# SCH004.net
KiCad netlist of a schematic drawn in Altium Designer
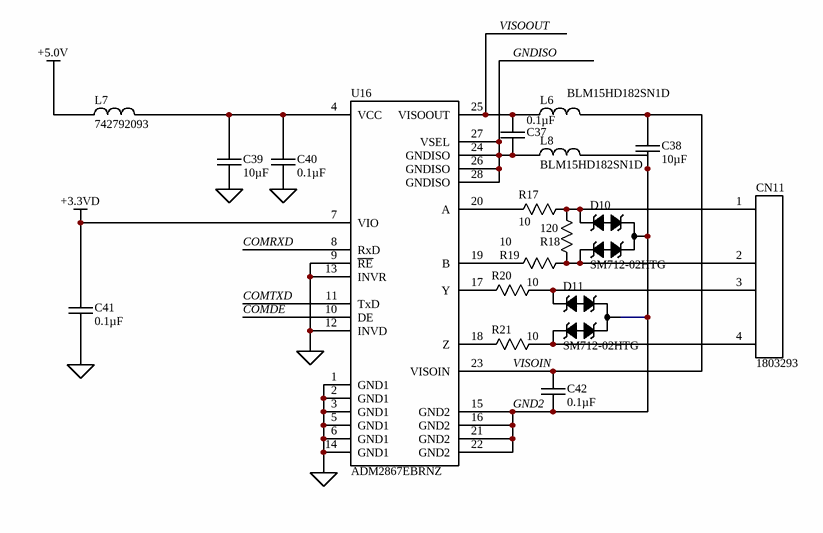
[diagram p0: SCH004.SchDoc]

(export (version "E")
  (design (tool "Eeschema 10.0.6"))
  (components
    (comp (ref "C37")
      (value "0.1µF")
      (footprint "CAPC2012X14N")
      (description "0.1µF/50V/±10% X7R Ceramic Chip Capacitor")
      (fields (field (name "MANUFACTURER") "Taiyo Yuden") (field (name "PARTNUMBER") "UMK212B7104KGHT"))
      (libsource (lib "EM411-202401-RMC001-001") (part "UMK212B7104KGHT"))
    )
    (comp (ref "C38")
      (value "10µF")
      (footprint "CAPC2012X14N")
      (description "10µF/25V 10% X5R Multi-Layer Ceramic Capacitor")
      (fields
        (field (name "MANUFACTURER") "Samsung Electro-Mechanics")
        (field (name "PARTNUMBER") "CL21A106KAFN3NE")
      )
      (libsource (lib "EM411-202401-RMC001-000-20240213-T10") (part "CL21A106KAFN3NE"))
    )
    (comp (ref "C39")
      (value "10µF")
      (footprint "CAPC2012X14N")
      (description "10µF/25V 10% X5R Multi-Layer Ceramic Capacitor")
      (fields
        (field (name "MANUFACTURER") "Samsung Electro-Mechanics")
        (field (name "PARTNUMBER") "CL21A106KAFN3NE")
      )
      (libsource (lib "EM411-202401-RMC001-000-20240213-T10") (part "CL21A106KAFN3NE"))
    )
    (comp (ref "C40")
      (value "0.1µF")
      (footprint "CAPC2012X14N")
      (description "0.1µF/50V/±10% X7R Ceramic Chip Capacitor")
      (fields (field (name "MANUFACTURER") "Taiyo Yuden") (field (name "PARTNUMBER") "UMK212B7104KGHT"))
      (libsource (lib "EM411-202401-RMC001-001") (part "UMK212B7104KGHT"))
    )
    (comp (ref "C41")
      (value "0.1µF")
      (footprint "CAPC2012X14N")
      (description "0.1µF/50V/±10% X7R Ceramic Chip Capacitor")
      (fields (field (name "MANUFACTURER") "Taiyo Yuden") (field (name "PARTNUMBER") "UMK212B7104KGHT"))
      (libsource (lib "EM411-202401-RMC001-001") (part "UMK212B7104KGHT"))
    )
    (comp (ref "C42")
      (value "0.1µF")
      (footprint "CAPC2012X14N")
      (description "0.1µF/50V/±10% X7R Ceramic Chip Capacitor")
      (fields (field (name "MANUFACTURER") "Taiyo Yuden") (field (name "PARTNUMBER") "UMK212B7104KGHT"))
      (libsource (lib "EM411-202401-RMC001-001") (part "UMK212B7104KGHT"))
    )
    (comp (ref "CN11")
      (value "1803293")
      (footprint "PHOENIX_1803293")
      (description "MC 1,5/4G-3,81 Pluggable Terminal Block 4 Pos 3.81mm pitch Through Hole Header")
      (fields (field (name "MANUFACTURER") "Phoenix Contact"))
      (libsource (lib "EM411-202401-RMC001-001") (part "1803293"))
    )
    (comp (ref "D10")
      (value "SM712-02HTG")
      (footprint "SOT95P237X112-3N")
      (description "SM712 Series 600W Asymmetrical TVS Diode Array")
      (fields (field (name "MANUFACTURER") "Littelfuse"))
      (libsource (lib "EM411-202401-RMC001-001") (part "SM712-02HTG"))
    )
    (comp (ref "D11")
      (value "SM712-02HTG")
      (footprint "SOT95P237X112-3N")
      (description "SM712 Series 600W Asymmetrical TVS Diode Array")
      (fields (field (name "MANUFACTURER") "Littelfuse"))
      (libsource (lib "EM411-202401-RMC001-001") (part "SM712-02HTG"))
    )
    (comp (ref "L6")
      (value "BLM15HD182SN1D")
      (footprint "INDC1005X06N")
      (description "GHz Noise Suppression Chip Ferrite Bead")
      (fields (field (name "MANUFACTURER") "Murata Electronics"))
      (libsource (lib "EM411-202401-RMC001-000-20240213-T10") (part "BLM15HD182SN1D"))
    )
    (comp (ref "L7")
      (value "742792093")
      (footprint "INDC2012X11N")
      (description "Multilayer SMD Ferrite")
      (fields (field (name "MANUFACTURER") "Wurth Elektronik"))
      (libsource (lib "EM411-202401-RMC001-001") (part "742792093"))
    )
    (comp (ref "L8")
      (value "BLM15HD182SN1D")
      (footprint "INDC1005X06N")
      (description "GHz Noise Suppression Chip Ferrite Bead")
      (fields (field (name "MANUFACTURER") "Murata Electronics"))
      (libsource (lib "EM411-202401-RMC001-000-20240213-T10") (part "BLM15HD182SN1D"))
    )
    (comp (ref "R17")
      (value "10")
      (footprint "RESC1608X06N")
      (description "10, 1%, 0.33W Pulse Proof, High Power Thick Film Chip Resistor")
      (fields
        (field (name "MANUFACTURER") "Vishay Intertechnology")
        (field (name "PARTNUMBER") "CRCW060310R0FKEAHP")
      )
      (libsource (lib "EM411-202401-RMC001-001") (part "CRCW060310R0FKEAHP"))
    )
    (comp (ref "R18")
      (value "120")
      (footprint "RESC2012X06N")
      (description "120, 1%, 0.125W Thick Film Chip Resistor")
      (fields (field (name "MANUFACTURER") "Bourns") (field (name "PARTNUMBER") "CR0805-FX-1200ELF"))
      (libsource (lib "EM411-202401-RMC001-001") (part "CR0805-FX-1200ELF"))
    )
    (comp (ref "R19")
      (value "10")
      (footprint "RESC1608X06N")
      (description "10, 1%, 0.33W Pulse Proof, High Power Thick Film Chip Resistor")
      (fields
        (field (name "MANUFACTURER") "Vishay Intertechnology")
        (field (name "PARTNUMBER") "CRCW060310R0FKEAHP")
      )
      (libsource (lib "EM411-202401-RMC001-001") (part "CRCW060310R0FKEAHP"))
    )
    (comp (ref "R20")
      (value "10")
      (footprint "RESC1608X06N")
      (description "10, 1%, 0.33W Pulse Proof, High Power Thick Film Chip Resistor")
      (fields
        (field (name "MANUFACTURER") "Vishay Intertechnology")
        (field (name "PARTNUMBER") "CRCW060310R0FKEAHP")
      )
      (libsource (lib "EM411-202401-RMC001-001") (part "CRCW060310R0FKEAHP"))
    )
    (comp (ref "R21")
      (value "10")
      (footprint "RESC1608X06N")
      (description "10, 1%, 0.33W Pulse Proof, High Power Thick Film Chip Resistor")
      (fields
        (field (name "MANUFACTURER") "Vishay Intertechnology")
        (field (name "PARTNUMBER") "CRCW060310R0FKEAHP")
      )
      (libsource (lib "EM411-202401-RMC001-001") (part "CRCW060310R0FKEAHP"))
    )
    (comp (ref "U16")
      (value "ADM2867EBRNZ")
      (footprint "SOP65P1030X265-28N")
      (description "5.7 kV RMS Signal and Power Isolated RS-485 Transceiver with ±15 kV IEC ESD")
      (fields (field (name "MANUFACTURER") "Analog Devices, Inc."))
      (libsource (lib "EM411-202401-RMC001-001") (part "ADM2867EBRNZ"))
    )
  )
  (nets
    (net (code "1") (name "+3.3VD") (class "Default")
      (node (ref "C41") (pin "1") (pinfunction "1_1") (pintype "passive"))
      (node (ref "U16") (pin "7") (pinfunction "VIO_7") (pintype "passive"))
    )
    (net (code "2") (name "+5.0V") (class "Default")
      (node (ref "L7") (pin "1") (pinfunction "1_1") (pintype "passive"))
    )
    (net (code "3") (name "/COMDE") (class "Default")
      (node (ref "U16") (pin "10") (pinfunction "DE_10") (pintype "passive"))
    )
    (net (code "4") (name "/COMRXD") (class "Default")
      (node (ref "U16") (pin "8") (pinfunction "RxD_8") (pintype "passive"))
    )
    (net (code "5") (name "/COMTXD") (class "Default")
      (node (ref "U16") (pin "11") (pinfunction "TxD_11") (pintype "passive"))
    )
    (net (code "6") (name "/GND2") (class "Default")
      (node (ref "C38") (pin "2") (pinfunction "2_2") (pintype "passive"))
      (node (ref "C42") (pin "2") (pinfunction "2_2") (pintype "passive"))
      (node (ref "D10") (pin "3") (pinfunction "3_3") (pintype "passive"))
      (node (ref "D11") (pin "3") (pinfunction "3_3") (pintype "passive"))
      (node (ref "L8") (pin "2") (pinfunction "2_2") (pintype "passive"))
      (node (ref "U16") (pin "15") (pinfunction "GND2_15") (pintype "passive"))
      (node (ref "U16") (pin "16") (pinfunction "GND2_16") (pintype "passive"))
      (node (ref "U16") (pin "21") (pinfunction "GND2_21") (pintype "passive"))
      (node (ref "U16") (pin "22") (pinfunction "GND2_22") (pintype "passive"))
    )
    (net (code "7") (name "/GNDISO") (class "Default")
      (node (ref "C37") (pin "2") (pinfunction "2_2") (pintype "passive"))
      (node (ref "L8") (pin "1") (pinfunction "1_1") (pintype "passive"))
      (node (ref "U16") (pin "24") (pinfunction "GNDISO_24") (pintype "passive"))
      (node (ref "U16") (pin "26") (pinfunction "GNDISO_26") (pintype "passive"))
      (node (ref "U16") (pin "27") (pinfunction "VSEL_27") (pintype "passive"))
      (node (ref "U16") (pin "28") (pinfunction "GNDISO_28") (pintype "passive"))
    )
    (net (code "8") (name "/VISOIN") (class "Default")
      (node (ref "C38") (pin "1") (pinfunction "1_1") (pintype "passive"))
      (node (ref "C42") (pin "1") (pinfunction "1_1") (pintype "passive"))
      (node (ref "L6") (pin "2") (pinfunction "2_2") (pintype "passive"))
      (node (ref "U16") (pin "23") (pinfunction "VISOIN_23") (pintype "passive"))
    )
    (net (code "9") (name "/VISOOUT") (class "Default")
      (node (ref "C37") (pin "1") (pinfunction "1_1") (pintype "passive"))
      (node (ref "L6") (pin "1") (pinfunction "1_1") (pintype "passive"))
      (node (ref "U16") (pin "25") (pinfunction "VISOOUT_25") (pintype "passive"))
    )
    (net (code "10") (name "GND") (class "Default")
      (node (ref "C39") (pin "2") (pinfunction "2_2") (pintype "passive"))
      (node (ref "C40") (pin "2") (pinfunction "2_2") (pintype "passive"))
      (node (ref "C41") (pin "2") (pinfunction "2_2") (pintype "passive"))
      (node (ref "U16") (pin "1") (pinfunction "GND1_1") (pintype "power_in"))
      (node (ref "U16") (pin "12") (pinfunction "INVD_12") (pintype "passive"))
      (node (ref "U16") (pin "13") (pinfunction "INVR_13") (pintype "passive"))
      (node (ref "U16") (pin "14") (pinfunction "GND1_14") (pintype "power_in"))
      (node (ref "U16") (pin "2") (pinfunction "GND1_2") (pintype "power_in"))
      (node (ref "U16") (pin "3") (pinfunction "GND1_3") (pintype "power_in"))
      (node (ref "U16") (pin "5") (pinfunction "GND1_5") (pintype "power_in"))
      (node (ref "U16") (pin "6") (pinfunction "GND1_6") (pintype "power_in"))
      (node (ref "U16") (pin "9") (pinfunction "~{RE}_9") (pintype "passive"))
    )
    (net (code "11") (name "Net-(CN11-Pad1)") (class "Default")
      (node (ref "CN11") (pin "1") (pinfunction "1_1") (pintype "passive"))
      (node (ref "D10") (pin "1") (pinfunction "1_1") (pintype "passive"))
      (node (ref "R17") (pin "2") (pinfunction "2_2") (pintype "passive"))
      (node (ref "R18") (pin "2") (pinfunction "2_2") (pintype "passive"))
    )
    (net (code "12") (name "Net-(CN11-Pad2)") (class "Default")
      (node (ref "CN11") (pin "2") (pinfunction "2_2") (pintype "passive"))
      (node (ref "D10") (pin "2") (pinfunction "2_2") (pintype "passive"))
      (node (ref "R18") (pin "1") (pinfunction "1_1") (pintype "passive"))
      (node (ref "R19") (pin "2") (pinfunction "2_2") (pintype "passive"))
    )
    (net (code "13") (name "Net-(CN11-Pad3)") (class "Default")
      (node (ref "CN11") (pin "3") (pinfunction "3_3") (pintype "passive"))
      (node (ref "D11") (pin "1") (pinfunction "1_1") (pintype "passive"))
      (node (ref "R20") (pin "2") (pinfunction "2_2") (pintype "passive"))
    )
    (net (code "14") (name "Net-(CN11-Pad4)") (class "Default")
      (node (ref "CN11") (pin "4") (pinfunction "4_4") (pintype "passive"))
      (node (ref "D11") (pin "2") (pinfunction "2_2") (pintype "passive"))
      (node (ref "R21") (pin "2") (pinfunction "2_2") (pintype "passive"))
    )
    (net (code "15") (name "Net-(U16-A)") (class "Default")
      (node (ref "R17") (pin "1") (pinfunction "1_1") (pintype "passive"))
      (node (ref "U16") (pin "20") (pinfunction "A_20") (pintype "passive"))
    )
    (net (code "16") (name "Net-(U16-B)") (class "Default")
      (node (ref "R19") (pin "1") (pinfunction "1_1") (pintype "passive"))
      (node (ref "U16") (pin "19") (pinfunction "B_19") (pintype "passive"))
    )
    (net (code "17") (name "Net-(U16-VCC)") (class "Default")
      (node (ref "C39") (pin "1") (pinfunction "1_1") (pintype "passive"))
      (node (ref "C40") (pin "1") (pinfunction "1_1") (pintype "passive"))
      (node (ref "L7") (pin "2") (pinfunction "2_2") (pintype "passive"))
      (node (ref "U16") (pin "4") (pinfunction "VCC_4") (pintype "passive"))
    )
    (net (code "18") (name "Net-(U16-Y)") (class "Default")
      (node (ref "R20") (pin "1") (pinfunction "1_1") (pintype "passive"))
      (node (ref "U16") (pin "17") (pinfunction "Y_17") (pintype "passive"))
    )
    (net (code "19") (name "Net-(U16-Z)") (class "Default")
      (node (ref "R21") (pin "1") (pinfunction "1_1") (pintype "passive"))
      (node (ref "U16") (pin "18") (pinfunction "Z_18") (pintype "passive"))
    )
  )
)
